# RGBLED.net
KiCad netlist of a schematic drawn in EAGLE
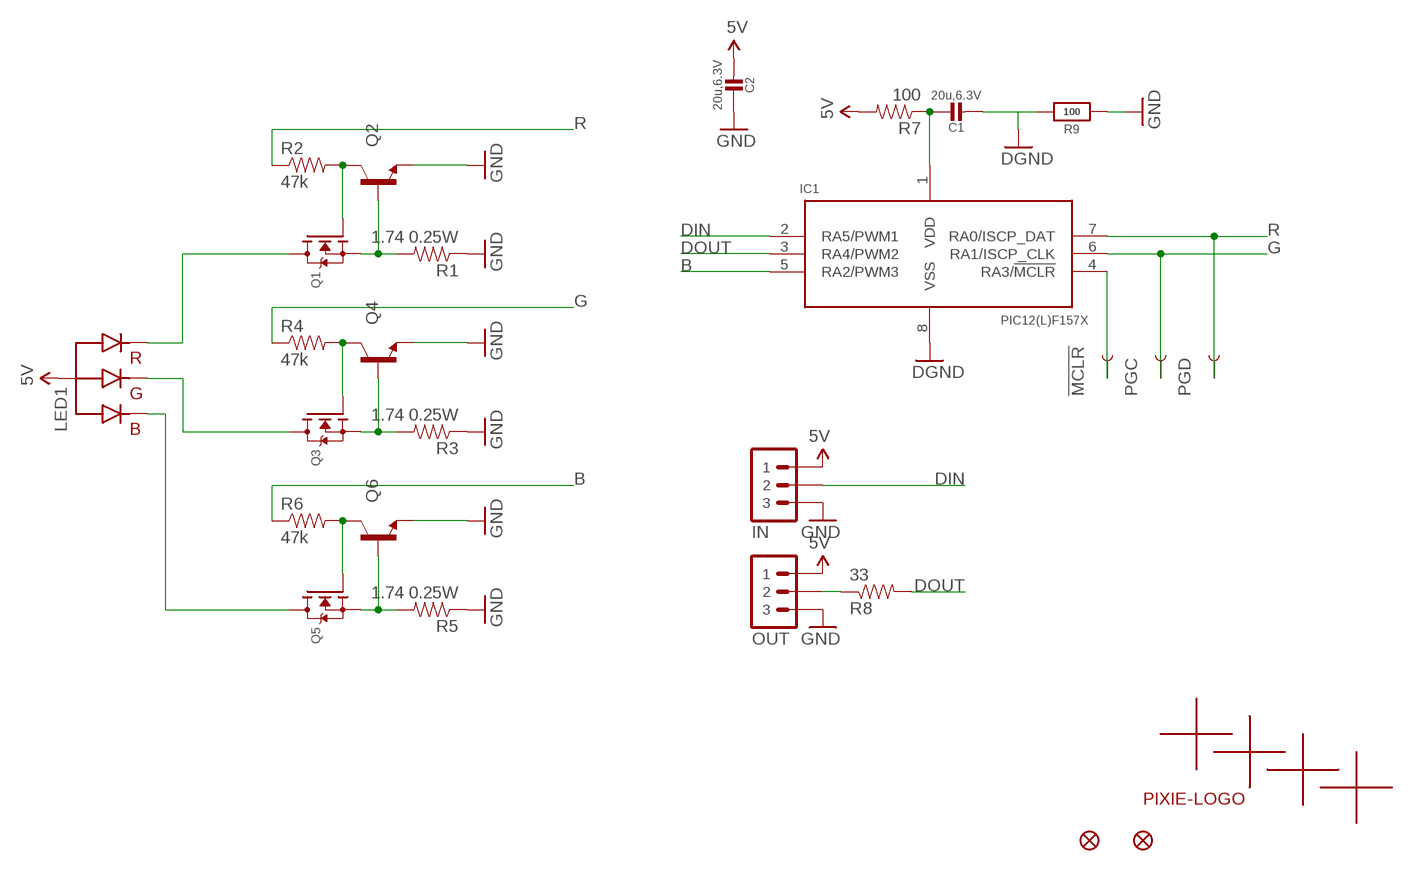
[diagram p0: schematic, sheet 1]

(export (version "E")
  (design (tool "Eeschema 10.0.6"))
  (components
    (comp (ref "!MCLR")
      (value "TEST-POINT3X4")
      (footprint "eagle-import:PAD.03X.04")
      (libsource (lib "eagle-import") (part "TEST-POINT3X4"))
    )
    (comp (ref "C1")
      (value "20u,6.3V")
      (footprint "eagle-import:_0805MP")
      (libsource (lib "eagle-import") (part "CAP_CERAMIC_0805MP"))
    )
    (comp (ref "C2")
      (value "20u,6.3V")
      (footprint "eagle-import:_0805MP")
      (libsource (lib "eagle-import") (part "CAP_CERAMIC_0805MP"))
    )
    (comp (ref "IC1")
      (value "PIC12(L)F157X")
      (footprint "eagle-import:MSOP-8")
      (libsource (lib "eagle-import") (part "PIC12(L)F157X"))
    )
    (comp (ref "IN")
      (value "M030.1PWR+SIG")
      (footprint "eagle-import:1X03-0.1PWR+SIG")
      (libsource (lib "eagle-import") (part "M030.1PWR+SIG"))
    )
    (comp (ref "LED1")
      (value "RGBLED_CA")
      (footprint "eagle-import:RGBLED3W4PIN")
      (libsource (lib "eagle-import") (part "RGBLED_CA"))
    )
    (comp (ref "OUT")
      (value "M030.1PWR+SIG")
      (footprint "eagle-import:1X03-0.1PWR+SIG")
      (libsource (lib "eagle-import") (part "M030.1PWR+SIG"))
    )
    (comp (ref "PGC")
      (value "TEST-POINT3X4")
      (footprint "eagle-import:PAD.03X.04")
      (libsource (lib "eagle-import") (part "TEST-POINT3X4"))
    )
    (comp (ref "PGD")
      (value "TEST-POINT3X4")
      (footprint "eagle-import:PAD.03X.04")
      (libsource (lib "eagle-import") (part "TEST-POINT3X4"))
    )
    (comp (ref "Q1")
      (value "IRLML2060TRPBF")
      (footprint "eagle-import:SOT23-3")
      (libsource (lib "eagle-import") (part "IRLML2060TRPBF"))
    )
    (comp (ref "Q2")
      (value "MMBT2222A")
      (footprint "eagle-import:SOT23-3")
      (libsource (lib "eagle-import") (part "MMBT2222A"))
    )
    (comp (ref "Q3")
      (value "IRLML2060TRPBF")
      (footprint "eagle-import:SOT23-3")
      (libsource (lib "eagle-import") (part "IRLML2060TRPBF"))
    )
    (comp (ref "Q4")
      (value "MMBT2222A")
      (footprint "eagle-import:SOT23-3")
      (libsource (lib "eagle-import") (part "MMBT2222A"))
    )
    (comp (ref "Q5")
      (value "IRLML2060TRPBF")
      (footprint "eagle-import:SOT23-3")
      (libsource (lib "eagle-import") (part "IRLML2060TRPBF"))
    )
    (comp (ref "Q6")
      (value "MMBT2222A")
      (footprint "eagle-import:SOT23-3")
      (libsource (lib "eagle-import") (part "MMBT2222A"))
    )
    (comp (ref "R1")
      (value "1.74 0.25W")
      (footprint "eagle-import:1206")
      (libsource (lib "eagle-import") (part "SparkFun-Resistors_RESISTOR1206"))
    )
    (comp (ref "R2")
      (value "47k")
      (footprint "eagle-import:0603-RES")
      (libsource (lib "eagle-import") (part "RESISTOR0603"))
    )
    (comp (ref "R3")
      (value "1.74 0.25W")
      (footprint "eagle-import:1206")
      (libsource (lib "eagle-import") (part "SparkFun-Resistors_RESISTOR1206"))
    )
    (comp (ref "R4")
      (value "47k")
      (footprint "eagle-import:0603-RES")
      (libsource (lib "eagle-import") (part "RESISTOR0603"))
    )
    (comp (ref "R5")
      (value "1.74 0.25W")
      (footprint "eagle-import:1206")
      (libsource (lib "eagle-import") (part "SparkFun-Resistors_RESISTOR1206"))
    )
    (comp (ref "R6")
      (value "47k")
      (footprint "eagle-import:0603-RES")
      (libsource (lib "eagle-import") (part "RESISTOR0603"))
    )
    (comp (ref "R7")
      (value "100")
      (footprint "eagle-import:0603-RES")
      (libsource (lib "eagle-import") (part "RESISTOR0603"))
    )
    (comp (ref "R8")
      (value "33")
      (footprint "eagle-import:0603-RES")
      (libsource (lib "eagle-import") (part "RESISTOR0603"))
    )
    (comp (ref "R9")
      (value "100")
      (footprint "eagle-import:_0603MP")
      (libsource (lib "eagle-import") (part "RESISTOR_0603MP"))
    )
    (comp (ref "U$1")
      (value "ALIGN_CROSS")
      (footprint "eagle-import:ALIGN_CROSS")
      (libsource (lib "eagle-import") (part "ALIGN_CROSS"))
    )
    (comp (ref "U$2")
      (value "ALIGN_CROSS")
      (footprint "eagle-import:ALIGN_CROSS")
      (libsource (lib "eagle-import") (part "ALIGN_CROSS"))
    )
    (comp (ref "U$3")
      (value "ALIGN_CROSS")
      (footprint "eagle-import:ALIGN_CROSS")
      (libsource (lib "eagle-import") (part "ALIGN_CROSS"))
    )
    (comp (ref "U$4")
      (value "ALIGN_CROSS")
      (footprint "eagle-import:ALIGN_CROSS")
      (libsource (lib "eagle-import") (part "ALIGN_CROSS"))
    )
    (comp (ref "U$5")
      (value "PIXIE-LOGO")
      (footprint "eagle-import:PIXIE-LOGO")
      (libsource (lib "eagle-import") (part "PIXIE-LOGO"))
    )
    (comp (ref "U$6")
      (value "FIDUCIAL\"\"")
      (footprint "eagle-import:FIDUCIAL_1MM")
      (libsource (lib "eagle-import") (part "FIDUCIAL{dblquote}{dblquote}"))
    )
    (comp (ref "U$7")
      (value "FIDUCIAL\"\"")
      (footprint "eagle-import:FIDUCIAL_1MM")
      (libsource (lib "eagle-import") (part "FIDUCIAL{dblquote}{dblquote}"))
    )
  )
  (nets
    (net (code "1") (name "/B") (class "Default")
      (node (ref "IC1") (pin "5") (pinfunction "RA2/PWM3_5") (pintype "bidirectional"))
      (node (ref "R6") (pin "1") (pinfunction "1_1") (pintype "passive"))
    )
    (net (code "2") (name "/DIN") (class "Default")
      (node (ref "IC1") (pin "2") (pinfunction "RA5/PWM1_2") (pintype "bidirectional"))
      (node (ref "IN") (pin "P$2") (pinfunction "2_P$2") (pintype "passive"))
    )
    (net (code "3") (name "/DOUT") (class "Default")
      (node (ref "IC1") (pin "3") (pinfunction "RA4/PWM2_3") (pintype "bidirectional"))
      (node (ref "R8") (pin "2") (pinfunction "2_2") (pintype "passive"))
    )
    (net (code "4") (name "/G") (class "Default")
      (node (ref "IC1") (pin "6") (pinfunction "RA1/ISCP_CLK_6") (pintype "bidirectional"))
      (node (ref "PGC") (pin "P$1") (pinfunction "1_P$1") (pintype "bidirectional"))
      (node (ref "R4") (pin "1") (pinfunction "1_1") (pintype "passive"))
    )
    (net (code "5") (name "/R") (class "Default")
      (node (ref "IC1") (pin "7") (pinfunction "RA0/ISCP_DAT_7") (pintype "bidirectional"))
      (node (ref "PGD") (pin "P$1") (pinfunction "1_P$1") (pintype "bidirectional"))
      (node (ref "R2") (pin "1") (pinfunction "1_1") (pintype "passive"))
    )
    (net (code "6") (name "5V") (class "Default")
      (node (ref "C2") (pin "2") (pinfunction "2_2") (pintype "passive"))
      (node (ref "IN") (pin "P$1") (pinfunction "1_P$1") (pintype "passive"))
      (node (ref "LED1") (pin "ANODE") (pinfunction "VCC_ANODE") (pintype "bidirectional"))
      (node (ref "OUT") (pin "P$1") (pinfunction "1_P$1") (pintype "passive"))
      (node (ref "R7") (pin "2") (pinfunction "2_2") (pintype "passive"))
    )
    (net (code "7") (name "DGND") (class "Default")
      (node (ref "C1") (pin "2") (pinfunction "2_2") (pintype "passive"))
      (node (ref "IC1") (pin "8") (pinfunction "VSS_8") (pintype "power_in"))
      (node (ref "R9") (pin "2") (pinfunction "2_2") (pintype "passive"))
    )
    (net (code "8") (name "GND") (class "Default")
      (node (ref "C2") (pin "1") (pinfunction "1_1") (pintype "passive"))
      (node (ref "IN") (pin "P$3") (pinfunction "3_P$3") (pintype "passive"))
      (node (ref "OUT") (pin "P$3") (pinfunction "3_P$3") (pintype "passive"))
      (node (ref "Q2") (pin "2") (pinfunction "E_2") (pintype "passive"))
      (node (ref "Q4") (pin "2") (pinfunction "E_2") (pintype "passive"))
      (node (ref "Q6") (pin "2") (pinfunction "E_2") (pintype "passive"))
      (node (ref "R1") (pin "1") (pinfunction "1_1") (pintype "passive"))
      (node (ref "R3") (pin "1") (pinfunction "1_1") (pintype "passive"))
      (node (ref "R5") (pin "1") (pinfunction "1_1") (pintype "passive"))
      (node (ref "R9") (pin "1") (pinfunction "1_1") (pintype "passive"))
    )
    (net (code "9") (name "Net-(!MCLR-1)") (class "Default")
      (node (ref "!MCLR") (pin "P$1") (pinfunction "1_P$1") (pintype "bidirectional"))
      (node (ref "IC1") (pin "4") (pinfunction "RA3/~{MCLR}_4") (pintype "bidirectional"))
    )
    (net (code "10") (name "Net-(IC1-VDD)") (class "Default")
      (node (ref "C1") (pin "1") (pinfunction "1_1") (pintype "passive"))
      (node (ref "IC1") (pin "1") (pinfunction "VDD_1") (pintype "power_in"))
      (node (ref "R7") (pin "1") (pinfunction "1_1") (pintype "passive"))
    )
    (net (code "11") (name "Net-(LED1-BLUE)") (class "Default")
      (node (ref "LED1") (pin "B") (pinfunction "BLUE_B") (pintype "bidirectional"))
      (node (ref "Q5") (pin "3") (pinfunction "D_3") (pintype "bidirectional"))
    )
    (net (code "12") (name "Net-(LED1-GREEN)") (class "Default")
      (node (ref "LED1") (pin "G") (pinfunction "GREEN_G") (pintype "bidirectional"))
      (node (ref "Q3") (pin "3") (pinfunction "D_3") (pintype "bidirectional"))
    )
    (net (code "13") (name "Net-(LED1-RED)") (class "Default")
      (node (ref "LED1") (pin "R") (pinfunction "RED_R") (pintype "bidirectional"))
      (node (ref "Q1") (pin "3") (pinfunction "D_3") (pintype "bidirectional"))
    )
    (net (code "14") (name "Net-(OUT-2)") (class "Default")
      (node (ref "OUT") (pin "P$2") (pinfunction "2_P$2") (pintype "passive"))
      (node (ref "R8") (pin "1") (pinfunction "1_1") (pintype "passive"))
    )
    (net (code "15") (name "Net-(Q1-G)") (class "Default")
      (node (ref "Q1") (pin "1") (pinfunction "G_1") (pintype "bidirectional"))
      (node (ref "Q2") (pin "3") (pinfunction "C_3") (pintype "passive"))
      (node (ref "R2") (pin "2") (pinfunction "2_2") (pintype "passive"))
    )
    (net (code "16") (name "Net-(Q1-S)") (class "Default")
      (node (ref "Q1") (pin "2") (pinfunction "S_2") (pintype "bidirectional"))
      (node (ref "Q2") (pin "1") (pinfunction "B_1") (pintype "passive"))
      (node (ref "R1") (pin "2") (pinfunction "2_2") (pintype "passive"))
    )
    (net (code "17") (name "Net-(Q3-G)") (class "Default")
      (node (ref "Q3") (pin "1") (pinfunction "G_1") (pintype "bidirectional"))
      (node (ref "Q4") (pin "3") (pinfunction "C_3") (pintype "passive"))
      (node (ref "R4") (pin "2") (pinfunction "2_2") (pintype "passive"))
    )
    (net (code "18") (name "Net-(Q3-S)") (class "Default")
      (node (ref "Q3") (pin "2") (pinfunction "S_2") (pintype "bidirectional"))
      (node (ref "Q4") (pin "1") (pinfunction "B_1") (pintype "passive"))
      (node (ref "R3") (pin "2") (pinfunction "2_2") (pintype "passive"))
    )
    (net (code "19") (name "Net-(Q5-G)") (class "Default")
      (node (ref "Q5") (pin "1") (pinfunction "G_1") (pintype "bidirectional"))
      (node (ref "Q6") (pin "3") (pinfunction "C_3") (pintype "passive"))
      (node (ref "R6") (pin "2") (pinfunction "2_2") (pintype "passive"))
    )
    (net (code "20") (name "Net-(Q5-S)") (class "Default")
      (node (ref "Q5") (pin "2") (pinfunction "S_2") (pintype "bidirectional"))
      (node (ref "Q6") (pin "1") (pinfunction "B_1") (pintype "passive"))
      (node (ref "R5") (pin "2") (pinfunction "2_2") (pintype "passive"))
    )
  )
)
